# board2.net
KiCad netlist of a schematic drawn in EAGLE
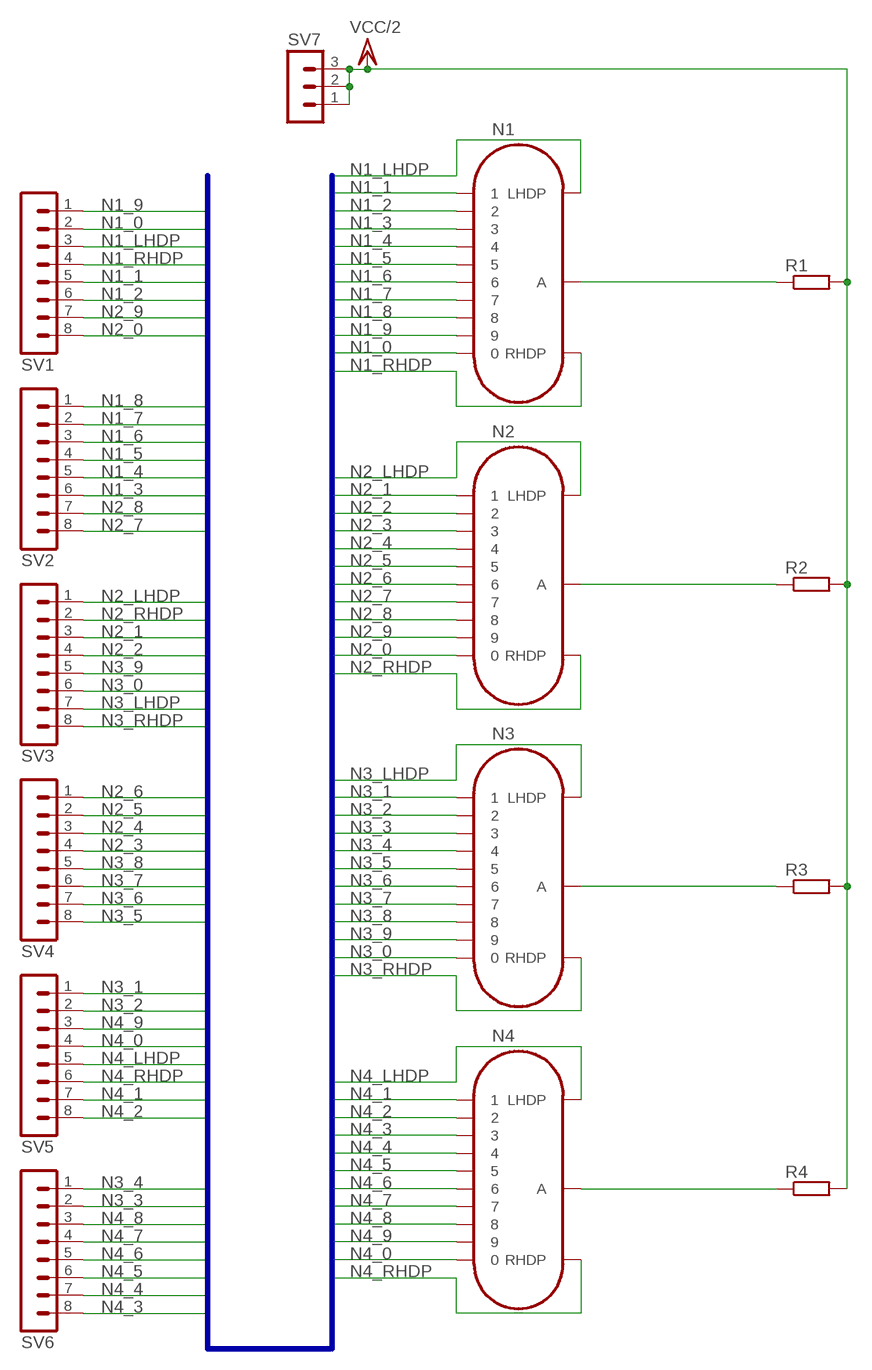
[diagram p0: schematic, sheet 1]

(export (version "E")
  (design (tool "Eeschema 10.0.6"))
  (components
    (comp (ref "N1")
      (value "IN-14")
      (footprint "eagle-import:IN-14")
      (libsource (lib "eagle-import") (part "IN-14"))
    )
    (comp (ref "N2")
      (value "IN-14")
      (footprint "eagle-import:IN-14")
      (libsource (lib "eagle-import") (part "IN-14"))
    )
    (comp (ref "N3")
      (value "IN-14")
      (footprint "eagle-import:IN-14")
      (libsource (lib "eagle-import") (part "IN-14"))
    )
    (comp (ref "N4")
      (value "IN-14")
      (footprint "eagle-import:IN-14")
      (libsource (lib "eagle-import") (part "IN-14"))
    )
    (comp (ref "R1")
      (value "R-EU_0207/7")
      (footprint "eagle-import:0207_7")
      (libsource (lib "eagle-import") (part "R-EU_0207/7"))
    )
    (comp (ref "R2")
      (value "R-EU_0207/7")
      (footprint "eagle-import:0207_7")
      (libsource (lib "eagle-import") (part "R-EU_0207/7"))
    )
    (comp (ref "R3")
      (value "R-EU_0207/7")
      (footprint "eagle-import:0207_7")
      (libsource (lib "eagle-import") (part "R-EU_0207/7"))
    )
    (comp (ref "R4")
      (value "R-EU_0207/7")
      (footprint "eagle-import:0207_7")
      (libsource (lib "eagle-import") (part "R-EU_0207/7"))
    )
    (comp (ref "SV1")
      (value "MA08-1")
      (footprint "eagle-import:MA08-1")
      (libsource (lib "eagle-import") (part "MA08-1"))
    )
    (comp (ref "SV2")
      (value "MA08-1")
      (footprint "eagle-import:MA08-1")
      (libsource (lib "eagle-import") (part "MA08-1"))
    )
    (comp (ref "SV3")
      (value "MA08-1")
      (footprint "eagle-import:MA08-1")
      (libsource (lib "eagle-import") (part "MA08-1"))
    )
    (comp (ref "SV4")
      (value "MA08-1")
      (footprint "eagle-import:MA08-1")
      (libsource (lib "eagle-import") (part "MA08-1"))
    )
    (comp (ref "SV5")
      (value "MA08-1")
      (footprint "eagle-import:MA08-1")
      (libsource (lib "eagle-import") (part "MA08-1"))
    )
    (comp (ref "SV6")
      (value "MA08-1")
      (footprint "eagle-import:MA08-1")
      (libsource (lib "eagle-import") (part "MA08-1"))
    )
    (comp (ref "SV7")
      (value "MA03-1")
      (footprint "eagle-import:MA03-1")
      (libsource (lib "eagle-import") (part "MA03-1"))
    )
  )
  (nets
    (net (code "1") (name "/N1_0") (class "Default")
      (node (ref "N1") (pin "0") (pinfunction "0_0") (pintype "bidirectional"))
      (node (ref "SV1") (pin "2") (pinfunction "2_2") (pintype "passive"))
    )
    (net (code "2") (name "/N1_1") (class "Default")
      (node (ref "N1") (pin "1") (pinfunction "1_1") (pintype "bidirectional"))
      (node (ref "SV1") (pin "5") (pinfunction "5_5") (pintype "passive"))
    )
    (net (code "3") (name "/N1_2") (class "Default")
      (node (ref "N1") (pin "2") (pinfunction "2_2") (pintype "bidirectional"))
      (node (ref "SV1") (pin "6") (pinfunction "6_6") (pintype "passive"))
    )
    (net (code "4") (name "/N1_3") (class "Default")
      (node (ref "N1") (pin "3") (pinfunction "3_3") (pintype "bidirectional"))
      (node (ref "SV2") (pin "6") (pinfunction "6_6") (pintype "passive"))
    )
    (net (code "5") (name "/N1_4") (class "Default")
      (node (ref "N1") (pin "4") (pinfunction "4_4") (pintype "bidirectional"))
      (node (ref "SV2") (pin "5") (pinfunction "5_5") (pintype "passive"))
    )
    (net (code "6") (name "/N1_5") (class "Default")
      (node (ref "N1") (pin "5") (pinfunction "5_5") (pintype "bidirectional"))
      (node (ref "SV2") (pin "4") (pinfunction "4_4") (pintype "passive"))
    )
    (net (code "7") (name "/N1_6") (class "Default")
      (node (ref "N1") (pin "6") (pinfunction "6_6") (pintype "bidirectional"))
      (node (ref "SV2") (pin "3") (pinfunction "3_3") (pintype "passive"))
    )
    (net (code "8") (name "/N1_7") (class "Default")
      (node (ref "N1") (pin "7") (pinfunction "7_7") (pintype "bidirectional"))
      (node (ref "SV2") (pin "2") (pinfunction "2_2") (pintype "passive"))
    )
    (net (code "9") (name "/N1_8") (class "Default")
      (node (ref "N1") (pin "8") (pinfunction "8_8") (pintype "bidirectional"))
      (node (ref "SV2") (pin "1") (pinfunction "1_1") (pintype "passive"))
    )
    (net (code "10") (name "/N1_9") (class "Default")
      (node (ref "N1") (pin "9") (pinfunction "9_9") (pintype "bidirectional"))
      (node (ref "SV1") (pin "1") (pinfunction "1_1") (pintype "passive"))
    )
    (net (code "11") (name "/N1_LHDP") (class "Default")
      (node (ref "N1") (pin "LHDP") (pinfunction "LHDP_LHDP") (pintype "bidirectional"))
      (node (ref "SV1") (pin "3") (pinfunction "3_3") (pintype "passive"))
    )
    (net (code "12") (name "/N1_RHDP") (class "Default")
      (node (ref "N1") (pin "RHDP") (pinfunction "RHDP_RHDP") (pintype "bidirectional"))
      (node (ref "SV1") (pin "4") (pinfunction "4_4") (pintype "passive"))
    )
    (net (code "13") (name "/N2_0") (class "Default")
      (node (ref "N2") (pin "0") (pinfunction "0_0") (pintype "bidirectional"))
      (node (ref "SV1") (pin "8") (pinfunction "8_8") (pintype "passive"))
    )
    (net (code "14") (name "/N2_1") (class "Default")
      (node (ref "N2") (pin "1") (pinfunction "1_1") (pintype "bidirectional"))
      (node (ref "SV3") (pin "3") (pinfunction "3_3") (pintype "passive"))
    )
    (net (code "15") (name "/N2_2") (class "Default")
      (node (ref "N2") (pin "2") (pinfunction "2_2") (pintype "bidirectional"))
      (node (ref "SV3") (pin "4") (pinfunction "4_4") (pintype "passive"))
    )
    (net (code "16") (name "/N2_3") (class "Default")
      (node (ref "N2") (pin "3") (pinfunction "3_3") (pintype "bidirectional"))
      (node (ref "SV4") (pin "4") (pinfunction "4_4") (pintype "passive"))
    )
    (net (code "17") (name "/N2_4") (class "Default")
      (node (ref "N2") (pin "4") (pinfunction "4_4") (pintype "bidirectional"))
      (node (ref "SV4") (pin "3") (pinfunction "3_3") (pintype "passive"))
    )
    (net (code "18") (name "/N2_5") (class "Default")
      (node (ref "N2") (pin "5") (pinfunction "5_5") (pintype "bidirectional"))
      (node (ref "SV4") (pin "2") (pinfunction "2_2") (pintype "passive"))
    )
    (net (code "19") (name "/N2_6") (class "Default")
      (node (ref "N2") (pin "6") (pinfunction "6_6") (pintype "bidirectional"))
      (node (ref "SV4") (pin "1") (pinfunction "1_1") (pintype "passive"))
    )
    (net (code "20") (name "/N2_7") (class "Default")
      (node (ref "N2") (pin "7") (pinfunction "7_7") (pintype "bidirectional"))
      (node (ref "SV2") (pin "8") (pinfunction "8_8") (pintype "passive"))
    )
    (net (code "21") (name "/N2_8") (class "Default")
      (node (ref "N2") (pin "8") (pinfunction "8_8") (pintype "bidirectional"))
      (node (ref "SV2") (pin "7") (pinfunction "7_7") (pintype "passive"))
    )
    (net (code "22") (name "/N2_9") (class "Default")
      (node (ref "N2") (pin "9") (pinfunction "9_9") (pintype "bidirectional"))
      (node (ref "SV1") (pin "7") (pinfunction "7_7") (pintype "passive"))
    )
    (net (code "23") (name "/N2_LHDP") (class "Default")
      (node (ref "N2") (pin "LHDP") (pinfunction "LHDP_LHDP") (pintype "bidirectional"))
      (node (ref "SV3") (pin "1") (pinfunction "1_1") (pintype "passive"))
    )
    (net (code "24") (name "/N2_RHDP") (class "Default")
      (node (ref "N2") (pin "RHDP") (pinfunction "RHDP_RHDP") (pintype "bidirectional"))
      (node (ref "SV3") (pin "2") (pinfunction "2_2") (pintype "passive"))
    )
    (net (code "25") (name "/N3_0") (class "Default")
      (node (ref "N3") (pin "0") (pinfunction "0_0") (pintype "bidirectional"))
      (node (ref "SV3") (pin "6") (pinfunction "6_6") (pintype "passive"))
    )
    (net (code "26") (name "/N3_1") (class "Default")
      (node (ref "N3") (pin "1") (pinfunction "1_1") (pintype "bidirectional"))
      (node (ref "SV5") (pin "1") (pinfunction "1_1") (pintype "passive"))
    )
    (net (code "27") (name "/N3_2") (class "Default")
      (node (ref "N3") (pin "2") (pinfunction "2_2") (pintype "bidirectional"))
      (node (ref "SV5") (pin "2") (pinfunction "2_2") (pintype "passive"))
    )
    (net (code "28") (name "/N3_3") (class "Default")
      (node (ref "N3") (pin "3") (pinfunction "3_3") (pintype "bidirectional"))
      (node (ref "SV6") (pin "2") (pinfunction "2_2") (pintype "passive"))
    )
    (net (code "29") (name "/N3_4") (class "Default")
      (node (ref "N3") (pin "4") (pinfunction "4_4") (pintype "bidirectional"))
      (node (ref "SV6") (pin "1") (pinfunction "1_1") (pintype "passive"))
    )
    (net (code "30") (name "/N3_5") (class "Default")
      (node (ref "N3") (pin "5") (pinfunction "5_5") (pintype "bidirectional"))
      (node (ref "SV4") (pin "8") (pinfunction "8_8") (pintype "passive"))
    )
    (net (code "31") (name "/N3_6") (class "Default")
      (node (ref "N3") (pin "6") (pinfunction "6_6") (pintype "bidirectional"))
      (node (ref "SV4") (pin "7") (pinfunction "7_7") (pintype "passive"))
    )
    (net (code "32") (name "/N3_7") (class "Default")
      (node (ref "N3") (pin "7") (pinfunction "7_7") (pintype "bidirectional"))
      (node (ref "SV4") (pin "6") (pinfunction "6_6") (pintype "passive"))
    )
    (net (code "33") (name "/N3_8") (class "Default")
      (node (ref "N3") (pin "8") (pinfunction "8_8") (pintype "bidirectional"))
      (node (ref "SV4") (pin "5") (pinfunction "5_5") (pintype "passive"))
    )
    (net (code "34") (name "/N3_9") (class "Default")
      (node (ref "N3") (pin "9") (pinfunction "9_9") (pintype "bidirectional"))
      (node (ref "SV3") (pin "5") (pinfunction "5_5") (pintype "passive"))
    )
    (net (code "35") (name "/N3_LHDP") (class "Default")
      (node (ref "N3") (pin "LHDP") (pinfunction "LHDP_LHDP") (pintype "bidirectional"))
      (node (ref "SV3") (pin "7") (pinfunction "7_7") (pintype "passive"))
    )
    (net (code "36") (name "/N3_RHDP") (class "Default")
      (node (ref "N3") (pin "RHDP") (pinfunction "RHDP_RHDP") (pintype "bidirectional"))
      (node (ref "SV3") (pin "8") (pinfunction "8_8") (pintype "passive"))
    )
    (net (code "37") (name "/N4_0") (class "Default")
      (node (ref "N4") (pin "0") (pinfunction "0_0") (pintype "bidirectional"))
      (node (ref "SV5") (pin "4") (pinfunction "4_4") (pintype "passive"))
    )
    (net (code "38") (name "/N4_1") (class "Default")
      (node (ref "N4") (pin "1") (pinfunction "1_1") (pintype "bidirectional"))
      (node (ref "SV5") (pin "7") (pinfunction "7_7") (pintype "passive"))
    )
    (net (code "39") (name "/N4_2") (class "Default")
      (node (ref "N4") (pin "2") (pinfunction "2_2") (pintype "bidirectional"))
      (node (ref "SV5") (pin "8") (pinfunction "8_8") (pintype "passive"))
    )
    (net (code "40") (name "/N4_3") (class "Default")
      (node (ref "N4") (pin "3") (pinfunction "3_3") (pintype "bidirectional"))
      (node (ref "SV6") (pin "8") (pinfunction "8_8") (pintype "passive"))
    )
    (net (code "41") (name "/N4_4") (class "Default")
      (node (ref "N4") (pin "4") (pinfunction "4_4") (pintype "bidirectional"))
      (node (ref "SV6") (pin "7") (pinfunction "7_7") (pintype "passive"))
    )
    (net (code "42") (name "/N4_5") (class "Default")
      (node (ref "N4") (pin "5") (pinfunction "5_5") (pintype "bidirectional"))
      (node (ref "SV6") (pin "6") (pinfunction "6_6") (pintype "passive"))
    )
    (net (code "43") (name "/N4_6") (class "Default")
      (node (ref "N4") (pin "6") (pinfunction "6_6") (pintype "bidirectional"))
      (node (ref "SV6") (pin "5") (pinfunction "5_5") (pintype "passive"))
    )
    (net (code "44") (name "/N4_7") (class "Default")
      (node (ref "N4") (pin "7") (pinfunction "7_7") (pintype "bidirectional"))
      (node (ref "SV6") (pin "4") (pinfunction "4_4") (pintype "passive"))
    )
    (net (code "45") (name "/N4_8") (class "Default")
      (node (ref "N4") (pin "8") (pinfunction "8_8") (pintype "bidirectional"))
      (node (ref "SV6") (pin "3") (pinfunction "3_3") (pintype "passive"))
    )
    (net (code "46") (name "/N4_9") (class "Default")
      (node (ref "N4") (pin "9") (pinfunction "9_9") (pintype "bidirectional"))
      (node (ref "SV5") (pin "3") (pinfunction "3_3") (pintype "passive"))
    )
    (net (code "47") (name "/N4_LHDP") (class "Default")
      (node (ref "N4") (pin "LHDP") (pinfunction "LHDP_LHDP") (pintype "bidirectional"))
      (node (ref "SV5") (pin "5") (pinfunction "5_5") (pintype "passive"))
    )
    (net (code "48") (name "/N4_RHDP") (class "Default")
      (node (ref "N4") (pin "RHDP") (pinfunction "RHDP_RHDP") (pintype "bidirectional"))
      (node (ref "SV5") (pin "6") (pinfunction "6_6") (pintype "passive"))
    )
    (net (code "49") (name "Net-(N1-PadA)") (class "Default")
      (node (ref "N1") (pin "A") (pinfunction "A_A") (pintype "bidirectional"))
      (node (ref "R1") (pin "1") (pinfunction "1_1") (pintype "passive"))
    )
    (net (code "50") (name "Net-(N2-PadA)") (class "Default")
      (node (ref "N2") (pin "A") (pinfunction "A_A") (pintype "bidirectional"))
      (node (ref "R2") (pin "1") (pinfunction "1_1") (pintype "passive"))
    )
    (net (code "51") (name "Net-(N3-PadA)") (class "Default")
      (node (ref "N3") (pin "A") (pinfunction "A_A") (pintype "bidirectional"))
      (node (ref "R3") (pin "1") (pinfunction "1_1") (pintype "passive"))
    )
    (net (code "52") (name "Net-(N4-PadA)") (class "Default")
      (node (ref "N4") (pin "A") (pinfunction "A_A") (pintype "bidirectional"))
      (node (ref "R4") (pin "1") (pinfunction "1_1") (pintype "passive"))
    )
    (net (code "53") (name "VCC{slash}2") (class "Default")
      (node (ref "R1") (pin "2") (pinfunction "2_2") (pintype "passive"))
      (node (ref "R2") (pin "2") (pinfunction "2_2") (pintype "passive"))
      (node (ref "R3") (pin "2") (pinfunction "2_2") (pintype "passive"))
      (node (ref "R4") (pin "2") (pinfunction "2_2") (pintype "passive"))
      (node (ref "SV7") (pin "1") (pinfunction "1_1") (pintype "passive"))
      (node (ref "SV7") (pin "2") (pinfunction "2_2") (pintype "passive"))
      (node (ref "SV7") (pin "3") (pinfunction "3_3") (pintype "passive"))
    )
  )
)
